# NeopixelExtension.net
KiCad netlist of a schematic drawn in EAGLE
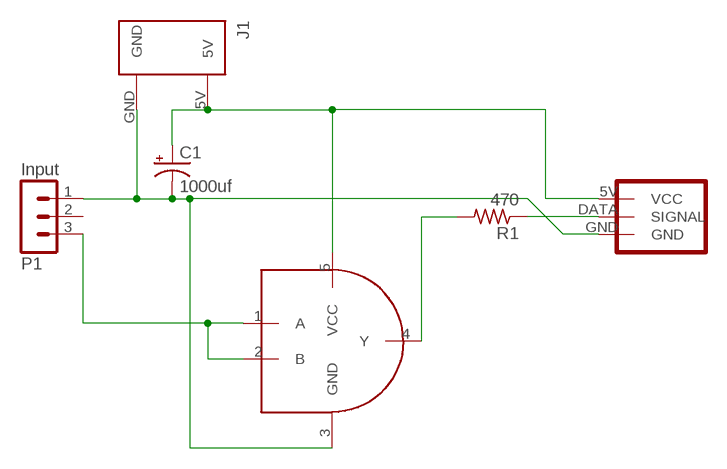
[diagram p0: schematic, sheet 1]

(export (version "E")
  (design (tool "Eeschema 10.0.6"))
  (components
    (comp (ref "C1")
      (value "1000uf")
      (footprint "eagle-import:E5-10,5")
      (libsource (lib "eagle-import") (part "CPOL-USE5-10.5"))
    )
    (comp (ref "J1")
      (value "POWER")
      (footprint "eagle-import:POWER")
      (libsource (lib "eagle-import") (part "POWER"))
    )
    (comp (ref "P1")
      (value "Input")
      (footprint "eagle-import:MA03-1")
      (libsource (lib "eagle-import") (part "MA03-1"))
    )
    (comp (ref "R1")
      (value "470")
      (footprint "eagle-import:R1206")
      (libsource (lib "eagle-import") (part "R-US_R1206"))
    )
    (comp (ref "U$2")
      (value "NEOPIXEL1")
      (footprint "eagle-import:NEODIRECTSOLDERORMA03-1")
      (libsource (lib "eagle-import") (part "NEOPIXEL1"))
    )
    (comp (ref "U1")
      (value "74AHCT1G08")
      (footprint "eagle-import:SOT25")
      (libsource (lib "eagle-import") (part "74AHCT1G08"))
    )
  )
  (nets
    (net (code "1") (name "Net-(U$2-SIGNAL)") (class "Default")
      (node (ref "R1") (pin "1") (pinfunction "1_1") (pintype "passive"))
      (node (ref "U$2") (pin "DATA") (pinfunction "SIGNAL_DATA") (pintype "bidirectional"))
    )
    (net (code "2") (name "Net-(U$2-VCC)") (class "Default")
      (node (ref "C1") (pin "+") (pinfunction "+_+") (pintype "passive"))
      (node (ref "J1") (pin "5V") (pinfunction "5V_5V") (pintype "power_in"))
      (node (ref "U$2") (pin "5V") (pinfunction "VCC_5V") (pintype "power_in"))
      (node (ref "U1") (pin "5") (pinfunction "VCC_5") (pintype "bidirectional"))
    )
    (net (code "3") (name "Net-(U1-A)") (class "Default")
      (node (ref "P1") (pin "3") (pinfunction "3_3") (pintype "passive"))
      (node (ref "U1") (pin "1") (pinfunction "A_1") (pintype "bidirectional"))
      (node (ref "U1") (pin "2") (pinfunction "B_2") (pintype "bidirectional"))
    )
    (net (code "4") (name "Net-(U1-GND)") (class "Default")
      (node (ref "C1") (pin "-") (pinfunction "-_-") (pintype "passive"))
      (node (ref "J1") (pin "GND") (pinfunction "GND_GND") (pintype "power_in"))
      (node (ref "P1") (pin "1") (pinfunction "1_1") (pintype "passive"))
      (node (ref "U$2") (pin "GND") (pinfunction "GND_GND") (pintype "power_in"))
      (node (ref "U1") (pin "3") (pinfunction "GND_3") (pintype "bidirectional"))
    )
    (net (code "5") (name "Net-(U1-Y)") (class "Default")
      (node (ref "R1") (pin "2") (pinfunction "2_2") (pintype "passive"))
      (node (ref "U1") (pin "4") (pinfunction "Y_4") (pintype "bidirectional"))
    )
    (net (code "6") (name "unconnected-(P1-Pad2)") (class "Default")
      (node (ref "P1") (pin "2") (pinfunction "2_2") (pintype "passive"))
    )
  )
)
